# Converter_Voltage_to_Current_2.net
KiCad netlist of a schematic drawn in Altium Designer
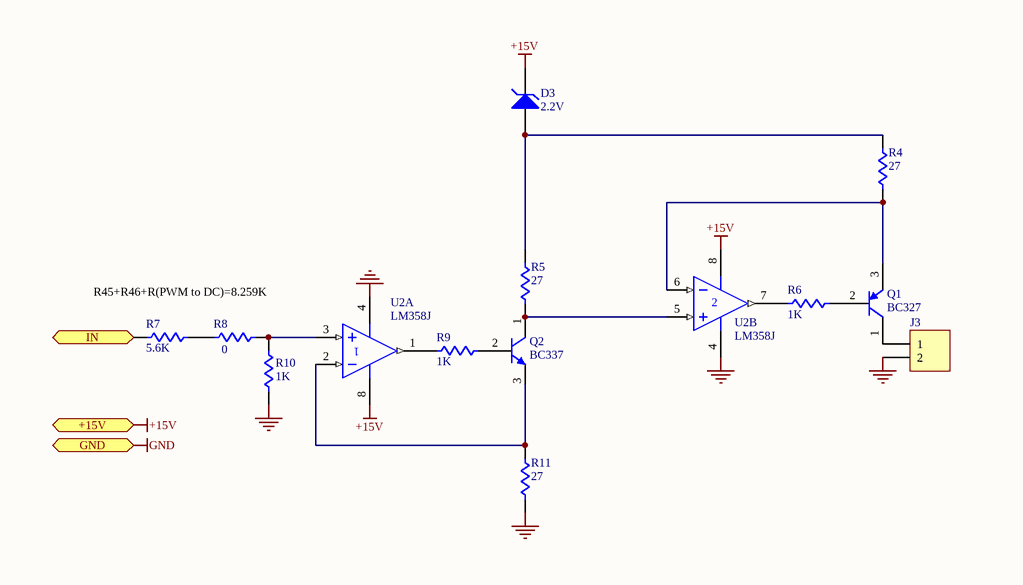
[diagram p0: Converter_Voltage to Current_2.SchDoc]

(export (version "E")
  (design (tool "Eeschema 10.0.6"))
  (components
    (comp (ref "D3")
      (value "2.2V")
      (footprint "DIODE-0.4")
      (description "Zener Diode")
      (fields
        (field (name "MANUFACTURER") "Generic Components")
        (field (name "Comment") "D Zener")
        (field (name "PUBLISHER") "Altium Limited")
      )
      (libsource (lib "Miscellaneous Devices") (part "D Zener"))
    )
    (comp (ref "J3")
      (value "Header 2")
      (footprint "Fonics_2PIN_1")
      (description "Header, 2-Pin")
      (fields (field (name "PUBLISHER") "Altium Limited"))
      (libsource (lib "Miscellaneous Connectors") (part "Header 2"))
    )
    (comp (ref "Q1")
      (value "PNP")
      (footprint "TO92C")
      (description "Silicon Bipolar Transistor")
      (fields (field (name "DEVICE") "BC327"))
      (libsource (lib "my Libraries") (part "PNP"))
    )
    (comp (ref "Q2")
      (value "BC337")
      (footprint "TO92C")
      (description "NPN Bipolar Transistor")
      (fields
        (field (name "MANUFACTURER") "Generic Components")
        (field (name "Comment") "NPN")
        (field (name "PUBLISHER") "Altium Limited")
      )
      (libsource (lib "Miscellaneous Devices") (part "NPN"))
    )
    (comp (ref "R4")
      (value "27")
      (footprint "AXIAL-0.4")
      (description "Resistor")
      (fields
        (field (name "MANUFACTURER") "Generic Components")
        (field (name "Comment") "Res1")
        (field (name "PUBLISHER") "Altium Limited")
      )
      (libsource (lib "Miscellaneous Devices") (part "Res1"))
    )
    (comp (ref "R5")
      (value "27")
      (footprint "AXIAL-0.4")
      (description "Resistor")
      (fields
        (field (name "MANUFACTURER") "Generic Components")
        (field (name "Comment") "Res1")
        (field (name "PUBLISHER") "Altium Limited")
      )
      (libsource (lib "Miscellaneous Devices") (part "Res1"))
    )
    (comp (ref "R6")
      (value "1K")
      (footprint "AXIAL-0.4")
      (description "Resistor")
      (fields
        (field (name "MANUFACTURER") "Generic Components")
        (field (name "Comment") "Res1")
        (field (name "PUBLISHER") "Altium Limited")
      )
      (libsource (lib "Miscellaneous Devices") (part "Res1"))
    )
    (comp (ref "R7")
      (value "5.6K")
      (footprint "AXIAL-0.4")
      (description "Resistor")
      (fields
        (field (name "MANUFACTURER") "Generic Components")
        (field (name "Comment") "Res1")
        (field (name "PUBLISHER") "Altium Limited")
      )
      (libsource (lib "Miscellaneous Devices") (part "Res1"))
    )
    (comp (ref "R8")
      (value "0")
      (footprint "AXIAL-0.4")
      (description "Resistor")
      (fields
        (field (name "MANUFACTURER") "Generic Components")
        (field (name "Comment") "Res1")
        (field (name "PUBLISHER") "Altium Limited")
      )
      (libsource (lib "Miscellaneous Devices") (part "Res1"))
    )
    (comp (ref "R9")
      (value "1K")
      (footprint "AXIAL-0.4")
      (description "Resistor")
      (fields
        (field (name "MANUFACTURER") "Generic Components")
        (field (name "Comment") "Res1")
        (field (name "PUBLISHER") "Altium Limited")
      )
      (libsource (lib "Miscellaneous Devices") (part "Res1"))
    )
    (comp (ref "R10")
      (value "1K")
      (footprint "AXIAL-0.4")
      (description "Resistor")
      (fields
        (field (name "MANUFACTURER") "Generic Components")
        (field (name "Comment") "Res1")
        (field (name "PUBLISHER") "Altium Limited")
      )
      (libsource (lib "Miscellaneous Devices") (part "Res1"))
    )
    (comp (ref "R11")
      (value "27")
      (footprint "AXIAL-0.4")
      (description "Resistor")
      (fields
        (field (name "MANUFACTURER") "Generic Components")
        (field (name "Comment") "Res1")
        (field (name "PUBLISHER") "Altium Limited")
      )
      (libsource (lib "Miscellaneous Devices") (part "Res1"))
    )
    (comp (ref "U2")
      (value "LM358J")
      (footprint "693-02")
      (description "Dual Low-Power Operational Amplifier")
      (fields (field (name "PUBLISHER") "Altium Limited"))
      (libsource (lib "Motorola Amplifier Operational Amplifier") (part "LM358J"))
    )
  )
  (nets
    (net (code "1") (name "+15V") (class "Default")
      (node (ref "D3") (pin "2") (pinfunction "K_2") (pintype "passive"))
      (node (ref "U2") (pin "8") (pinfunction "V+_8") (pintype "power_in"))
    )
    (net (code "2") (name "/IN") (class "Default")
      (node (ref "R7") (pin "1") (pinfunction "1_1") (pintype "passive"))
    )
    (net (code "3") (name "GND") (class "Default")
      (node (ref "J3") (pin "2") (pinfunction "2_2") (pintype "passive"))
      (node (ref "R10") (pin "2") (pinfunction "2_2") (pintype "passive"))
      (node (ref "R11") (pin "1") (pinfunction "1_1") (pintype "passive"))
      (node (ref "U2") (pin "4") (pinfunction "V-_4") (pintype "power_in"))
    )
    (net (code "4") (name "Net-(D3-A)") (class "Default")
      (node (ref "D3") (pin "1") (pinfunction "A_1") (pintype "passive"))
      (node (ref "R4") (pin "2") (pinfunction "2_2") (pintype "passive"))
      (node (ref "R5") (pin "2") (pinfunction "2_2") (pintype "passive"))
    )
    (net (code "5") (name "Net-(Q1-B)") (class "Default")
      (node (ref "Q1") (pin "2") (pinfunction "B_2") (pintype "passive"))
      (node (ref "R6") (pin "2") (pinfunction "2_2") (pintype "passive"))
    )
    (net (code "6") (name "Net-(Q1-C)") (class "Default")
      (node (ref "J3") (pin "1") (pinfunction "1_1") (pintype "passive"))
      (node (ref "Q1") (pin "1") (pinfunction "C_1") (pintype "passive"))
    )
    (net (code "7") (name "Net-(Q1-E)") (class "Default")
      (node (ref "Q1") (pin "3") (pinfunction "E_3") (pintype "passive"))
      (node (ref "R4") (pin "1") (pinfunction "1_1") (pintype "passive"))
      (node (ref "U2") (pin "6") (pinfunction "IN-_6") (pintype "input"))
    )
    (net (code "8") (name "Net-(Q2-B)") (class "Default")
      (node (ref "Q2") (pin "2") (pinfunction "B_2") (pintype "passive"))
      (node (ref "R9") (pin "2") (pinfunction "2_2") (pintype "passive"))
    )
    (net (code "9") (name "Net-(Q2-C)") (class "Default")
      (node (ref "Q2") (pin "1") (pinfunction "C_1") (pintype "passive"))
      (node (ref "R5") (pin "1") (pinfunction "1_1") (pintype "passive"))
      (node (ref "U2") (pin "5") (pinfunction "IN+_5") (pintype "input"))
    )
    (net (code "10") (name "Net-(Q2-E)") (class "Default")
      (node (ref "Q2") (pin "3") (pinfunction "E_3") (pintype "passive"))
      (node (ref "R11") (pin "2") (pinfunction "2_2") (pintype "passive"))
      (node (ref "U2") (pin "2") (pinfunction "IN-_2") (pintype "input"))
    )
    (net (code "11") (name "Net-(R7-Pad2)") (class "Default")
      (node (ref "R7") (pin "2") (pinfunction "2_2") (pintype "passive"))
      (node (ref "R8") (pin "1") (pinfunction "1_1") (pintype "passive"))
    )
    (net (code "12") (name "Net-(U2A-IN+)") (class "Default")
      (node (ref "R10") (pin "1") (pinfunction "1_1") (pintype "passive"))
      (node (ref "R8") (pin "2") (pinfunction "2_2") (pintype "passive"))
      (node (ref "U2") (pin "3") (pinfunction "IN+_3") (pintype "input"))
    )
    (net (code "13") (name "Net-(U2A-OUT)") (class "Default")
      (node (ref "R9") (pin "1") (pinfunction "1_1") (pintype "passive"))
      (node (ref "U2") (pin "1") (pinfunction "OUT_1") (pintype "output"))
    )
    (net (code "14") (name "Net-(U2B-OUT)") (class "Default")
      (node (ref "R6") (pin "1") (pinfunction "1_1") (pintype "passive"))
      (node (ref "U2") (pin "7") (pinfunction "OUT_7") (pintype "output"))
    )
  )
)
